# rev2-roadrunner.net
KiCad netlist of a schematic drawn in EAGLE
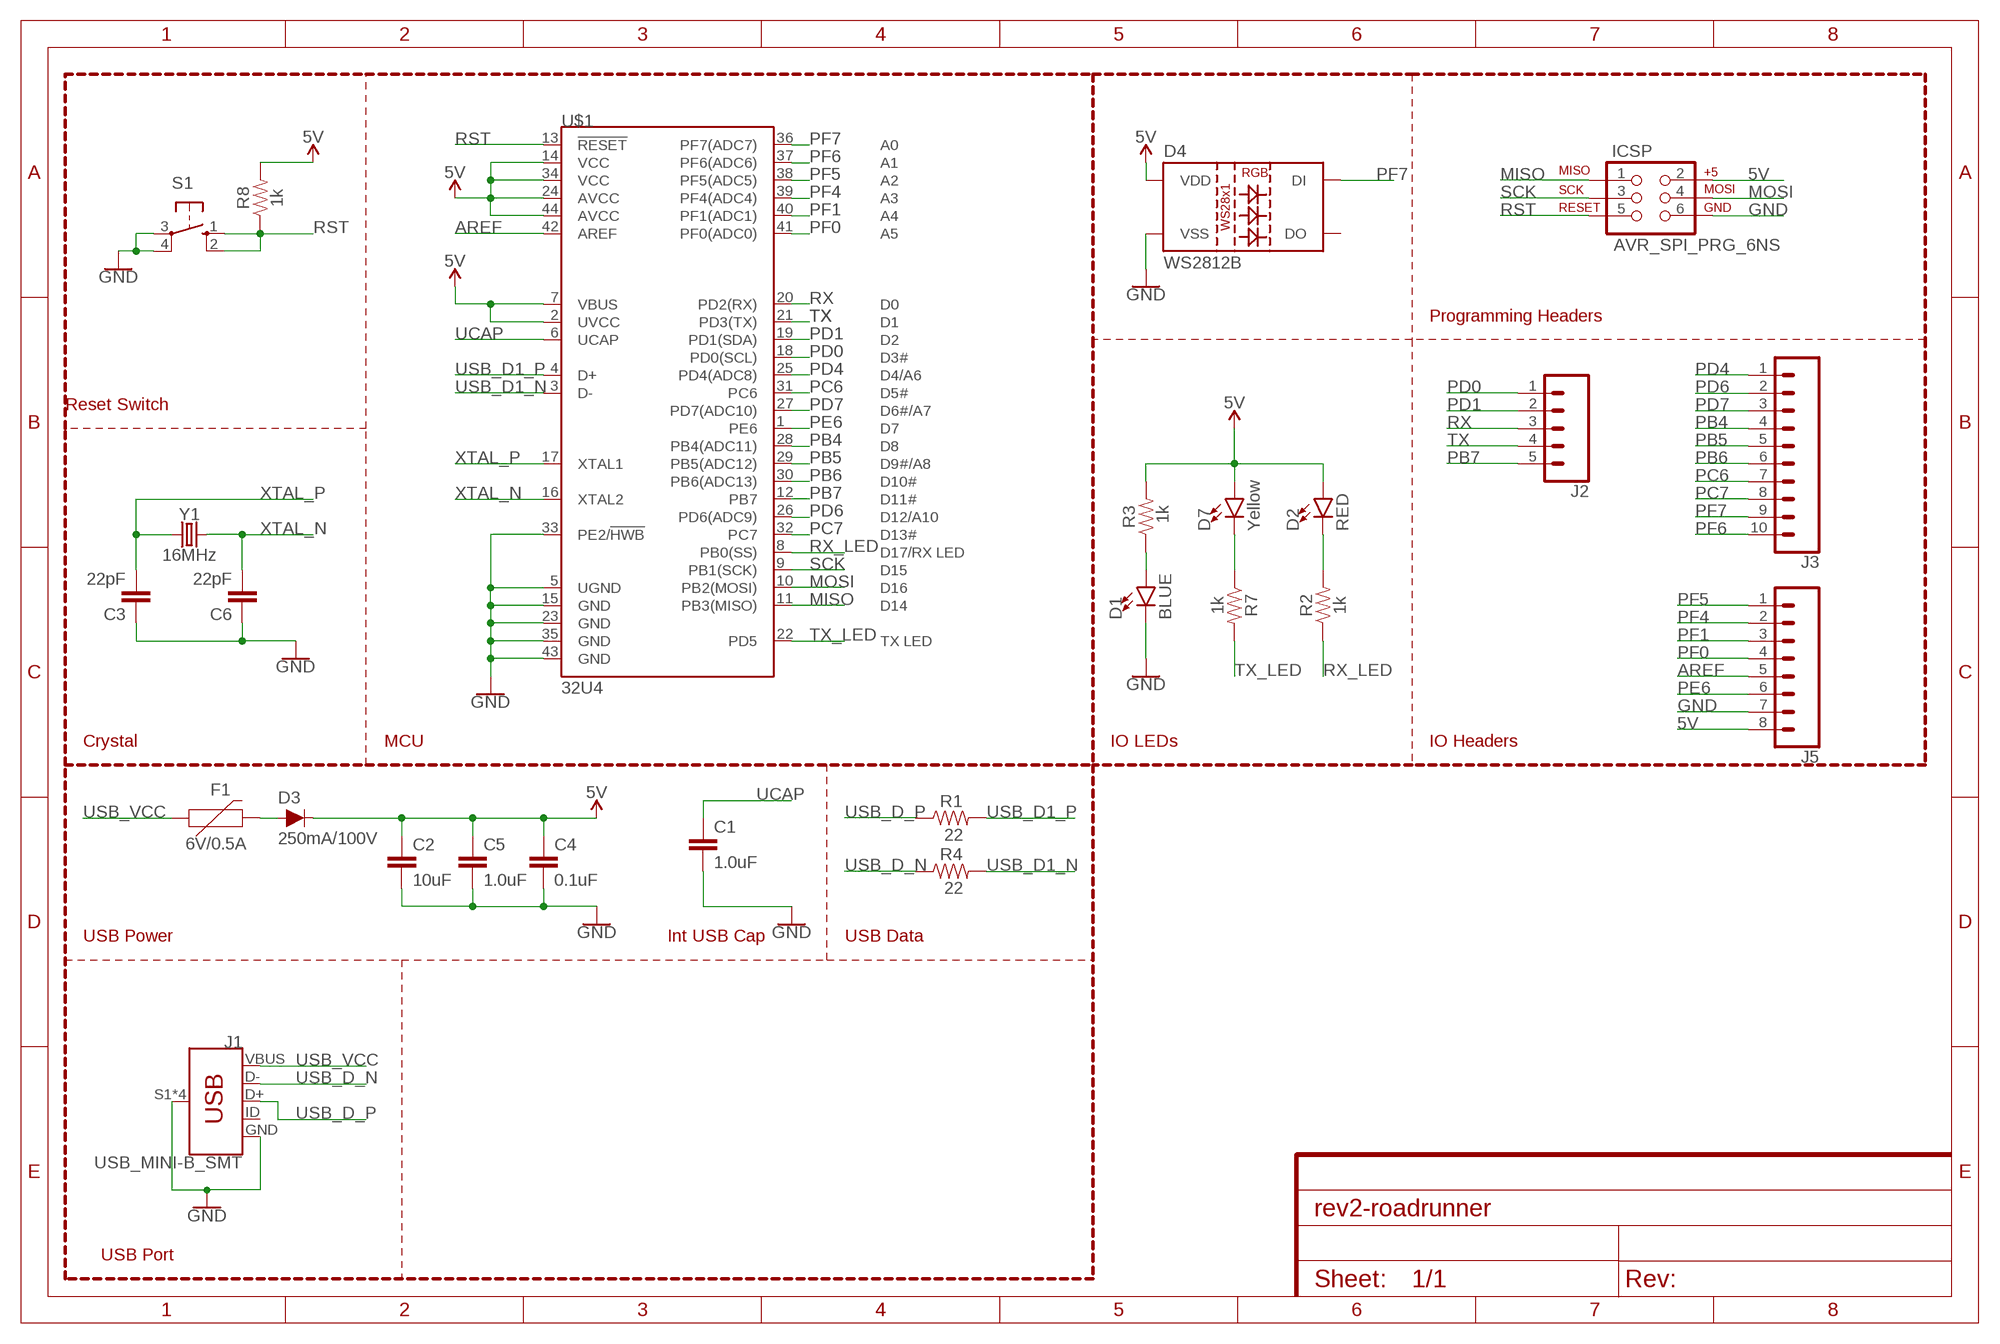
[diagram p0: schematic, sheet 1]

(export (version "E")
  (design (tool "Eeschema 10.0.6"))
  (components
    (comp (ref "C1")
      (value "1.0uF")
      (footprint "eagle-import:1206")
      (libsource (lib "eagle-import") (part "1.0UF-1206-50V-10%"))
    )
    (comp (ref "C2")
      (value "10uF")
      (footprint "eagle-import:1206")
      (libsource (lib "eagle-import") (part "10UF-1206-6.3V-20%"))
    )
    (comp (ref "C3")
      (value "22pF")
      (footprint "eagle-import:1206")
      (libsource (lib "eagle-import") (part "10UF-1206-6.3V-20%"))
    )
    (comp (ref "C4")
      (value "0.1uF")
      (footprint "eagle-import:1206")
      (libsource (lib "eagle-import") (part "1.0UF-1206-50V-10%"))
    )
    (comp (ref "C5")
      (value "1.0uF")
      (footprint "eagle-import:1206")
      (libsource (lib "eagle-import") (part "1.0UF-1206-50V-10%"))
    )
    (comp (ref "C6")
      (value "22pF")
      (footprint "eagle-import:1206")
      (libsource (lib "eagle-import") (part "10UF-1206-6.3V-20%"))
    )
    (comp (ref "D1")
      (value "BLUE")
      (footprint "eagle-import:LED-1206")
      (libsource (lib "eagle-import") (part "LED-BLUE1206"))
    )
    (comp (ref "D2")
      (value "RED")
      (footprint "eagle-import:LED-1206")
      (libsource (lib "eagle-import") (part "LED-RED1206"))
    )
    (comp (ref "D3")
      (value "250mA/100V")
      (footprint "eagle-import:SOD-323")
      (libsource (lib "eagle-import") (part "DIODE-BAS16J"))
    )
    (comp (ref "D4")
      (value "WS2812B")
      (footprint "eagle-import:WS2812B")
      (libsource (lib "eagle-import") (part "WS2812B"))
    )
    (comp (ref "D7")
      (value "Yellow")
      (footprint "eagle-import:LED-1206")
      (libsource (lib "eagle-import") (part "LED-YELLOWLILYPAD"))
    )
    (comp (ref "F1")
      (value "6V/0.5A")
      (footprint "eagle-import:1206")
      (libsource (lib "eagle-import") (part "PPTC_HALF-AMP"))
    )
    (comp (ref "ICSP")
      (value "AVR_SPI_PRG_6NS")
      (footprint "eagle-import:2X3-NS")
      (libsource (lib "eagle-import") (part "AVR_SPI_PRG_6NS"))
    )
    (comp (ref "J1")
      (value "USB_MINI-B_SMT")
      (footprint "eagle-import:USB-MINIB")
      (libsource (lib "eagle-import") (part "USB_MINI-B_SMT"))
    )
    (comp (ref "J2")
      (value "CONN_05")
      (footprint "eagle-import:1X05")
      (libsource (lib "eagle-import") (part "CONN_05"))
    )
    (comp (ref "J3")
      (value "CONN_10\"")
      (footprint "eagle-import:1X10")
      (libsource (lib "eagle-import") (part "CONN_10{dblquote}"))
    )
    (comp (ref "J5")
      (value "CONN_08\"")
      (footprint "eagle-import:1X08")
      (libsource (lib "eagle-import") (part "CONN_08{dblquote}"))
    )
    (comp (ref "R1")
      (value "22")
      (footprint "eagle-import:1206")
      (libsource (lib "eagle-import") (part "RESISTOR1206"))
    )
    (comp (ref "R2")
      (value "1k")
      (footprint "eagle-import:1206")
      (libsource (lib "eagle-import") (part "RESISTOR1206"))
    )
    (comp (ref "R3")
      (value "1k")
      (footprint "eagle-import:1206")
      (libsource (lib "eagle-import") (part "RESISTOR1206"))
    )
    (comp (ref "R4")
      (value "22")
      (footprint "eagle-import:1206")
      (libsource (lib "eagle-import") (part "RESISTOR1206"))
    )
    (comp (ref "R7")
      (value "1k")
      (footprint "eagle-import:1206")
      (libsource (lib "eagle-import") (part "RESISTOR1206"))
    )
    (comp (ref "R8")
      (value "1k")
      (footprint "eagle-import:1206")
      (libsource (lib "eagle-import") (part "RESISTOR1206"))
    )
    (comp (ref "S1")
      (value "10-XX")
      (footprint "eagle-import:B3F-10XX")
      (fields (field (name "MPN") "B3F-1000"))
      (libsource (lib "eagle-import") (part "10-XX"))
    )
    (comp (ref "U$1")
      (value "32U4")
      (footprint "eagle-import:TQFP44")
      (libsource (lib "eagle-import") (part "ATMEGA32U4TQFP-44"))
    )
    (comp (ref "Y1")
      (value "16MHz")
      (footprint "eagle-import:HC49US")
      (libsource (lib "eagle-import") (part "CRYSTAL-16MHZPTH-HC49US"))
    )
  )
  (nets
    (net (code "1") (name "/AREF") (class "Default")
      (node (ref "J5") (pin "5") (pinfunction "5_5") (pintype "passive"))
      (node (ref "U$1") (pin "42") (pinfunction "AREF_42") (pintype "bidirectional"))
    )
    (net (code "2") (name "/MISO") (class "Default")
      (node (ref "ICSP") (pin "1") (pinfunction "1_1") (pintype "passive"))
      (node (ref "U$1") (pin "11") (pinfunction "PB3(MISO)_11") (pintype "bidirectional"))
    )
    (net (code "3") (name "/MOSI") (class "Default")
      (node (ref "ICSP") (pin "4") (pinfunction "4_4") (pintype "passive"))
      (node (ref "U$1") (pin "10") (pinfunction "PB2(MOSI)_10") (pintype "bidirectional"))
    )
    (net (code "4") (name "/PB4") (class "Default")
      (node (ref "J3") (pin "4") (pinfunction "4_4") (pintype "passive"))
      (node (ref "U$1") (pin "28") (pinfunction "PB4(ADC11)_28") (pintype "bidirectional"))
    )
    (net (code "5") (name "/PB5") (class "Default")
      (node (ref "J3") (pin "5") (pinfunction "5_5") (pintype "passive"))
      (node (ref "U$1") (pin "29") (pinfunction "PB5(ADC12)_29") (pintype "bidirectional"))
    )
    (net (code "6") (name "/PB6") (class "Default")
      (node (ref "J3") (pin "6") (pinfunction "6_6") (pintype "passive"))
      (node (ref "U$1") (pin "30") (pinfunction "PB6(ADC13)_30") (pintype "bidirectional"))
    )
    (net (code "7") (name "/PB7") (class "Default")
      (node (ref "J2") (pin "5") (pinfunction "5_5") (pintype "passive"))
      (node (ref "U$1") (pin "12") (pinfunction "PB7_12") (pintype "bidirectional"))
    )
    (net (code "8") (name "/PC6") (class "Default")
      (node (ref "J3") (pin "7") (pinfunction "7_7") (pintype "passive"))
      (node (ref "U$1") (pin "31") (pinfunction "PC6_31") (pintype "bidirectional"))
    )
    (net (code "9") (name "/PC7") (class "Default")
      (node (ref "J3") (pin "8") (pinfunction "8_8") (pintype "passive"))
      (node (ref "U$1") (pin "32") (pinfunction "PC7_32") (pintype "bidirectional"))
    )
    (net (code "10") (name "/PD0") (class "Default")
      (node (ref "J2") (pin "1") (pinfunction "1_1") (pintype "passive"))
      (node (ref "U$1") (pin "18") (pinfunction "PD0(SCL)_18") (pintype "bidirectional"))
    )
    (net (code "11") (name "/PD1") (class "Default")
      (node (ref "J2") (pin "2") (pinfunction "2_2") (pintype "passive"))
      (node (ref "U$1") (pin "19") (pinfunction "PD1(SDA)_19") (pintype "bidirectional"))
    )
    (net (code "12") (name "/PD4") (class "Default")
      (node (ref "J3") (pin "1") (pinfunction "1_1") (pintype "passive"))
      (node (ref "U$1") (pin "25") (pinfunction "PD4(ADC8)_25") (pintype "bidirectional"))
    )
    (net (code "13") (name "/PD6") (class "Default")
      (node (ref "J3") (pin "2") (pinfunction "2_2") (pintype "passive"))
      (node (ref "U$1") (pin "26") (pinfunction "PD6(ADC9)_26") (pintype "bidirectional"))
    )
    (net (code "14") (name "/PD7") (class "Default")
      (node (ref "J3") (pin "3") (pinfunction "3_3") (pintype "passive"))
      (node (ref "U$1") (pin "27") (pinfunction "PD7(ADC10)_27") (pintype "bidirectional"))
    )
    (net (code "15") (name "/PE6") (class "Default")
      (node (ref "J5") (pin "6") (pinfunction "6_6") (pintype "passive"))
      (node (ref "U$1") (pin "1") (pinfunction "PE6_1") (pintype "bidirectional"))
    )
    (net (code "16") (name "/PF0") (class "Default")
      (node (ref "J5") (pin "4") (pinfunction "4_4") (pintype "passive"))
      (node (ref "U$1") (pin "41") (pinfunction "PF0(ADC0)_41") (pintype "bidirectional"))
    )
    (net (code "17") (name "/PF1") (class "Default")
      (node (ref "J5") (pin "3") (pinfunction "3_3") (pintype "passive"))
      (node (ref "U$1") (pin "40") (pinfunction "PF1(ADC1)_40") (pintype "bidirectional"))
    )
    (net (code "18") (name "/PF4") (class "Default")
      (node (ref "J5") (pin "2") (pinfunction "2_2") (pintype "passive"))
      (node (ref "U$1") (pin "39") (pinfunction "PF4(ADC4)_39") (pintype "bidirectional"))
    )
    (net (code "19") (name "/PF5") (class "Default")
      (node (ref "J5") (pin "1") (pinfunction "1_1") (pintype "passive"))
      (node (ref "U$1") (pin "38") (pinfunction "PF5(ADC5)_38") (pintype "bidirectional"))
    )
    (net (code "20") (name "/PF6") (class "Default")
      (node (ref "J3") (pin "10") (pinfunction "10_10") (pintype "passive"))
      (node (ref "U$1") (pin "37") (pinfunction "PF6(ADC6)_37") (pintype "bidirectional"))
    )
    (net (code "21") (name "/PF7") (class "Default")
      (node (ref "D4") (pin "4") (pinfunction "DI_4") (pintype "bidirectional"))
      (node (ref "J3") (pin "9") (pinfunction "9_9") (pintype "passive"))
      (node (ref "U$1") (pin "36") (pinfunction "PF7(ADC7)_36") (pintype "bidirectional"))
    )
    (net (code "22") (name "/RST") (class "Default")
      (node (ref "ICSP") (pin "5") (pinfunction "5_5") (pintype "passive"))
      (node (ref "R8") (pin "1") (pinfunction "1_1") (pintype "passive"))
      (node (ref "S1") (pin "1") (pinfunction "S_1") (pintype "passive"))
      (node (ref "S1") (pin "2") (pinfunction "S1_2") (pintype "passive"))
      (node (ref "U$1") (pin "13") (pinfunction "~{RESET}_13") (pintype "bidirectional"))
    )
    (net (code "23") (name "/RX") (class "Default")
      (node (ref "J2") (pin "3") (pinfunction "3_3") (pintype "passive"))
      (node (ref "U$1") (pin "20") (pinfunction "PD2(RX)_20") (pintype "bidirectional"))
    )
    (net (code "24") (name "/RX_LED") (class "Default")
      (node (ref "R2") (pin "1") (pinfunction "1_1") (pintype "passive"))
      (node (ref "U$1") (pin "8") (pinfunction "PB0(SS)_8") (pintype "bidirectional"))
    )
    (net (code "25") (name "/SCK") (class "Default")
      (node (ref "ICSP") (pin "3") (pinfunction "3_3") (pintype "passive"))
      (node (ref "U$1") (pin "9") (pinfunction "PB1(SCK)_9") (pintype "bidirectional"))
    )
    (net (code "26") (name "/TX") (class "Default")
      (node (ref "J2") (pin "4") (pinfunction "4_4") (pintype "passive"))
      (node (ref "U$1") (pin "21") (pinfunction "PD3(TX)_21") (pintype "bidirectional"))
    )
    (net (code "27") (name "/TX_LED") (class "Default")
      (node (ref "R7") (pin "2") (pinfunction "2_2") (pintype "passive"))
      (node (ref "U$1") (pin "22") (pinfunction "PD5_22") (pintype "bidirectional"))
    )
    (net (code "28") (name "/UCAP") (class "Default")
      (node (ref "C1") (pin "1") (pinfunction "1_1") (pintype "passive"))
      (node (ref "U$1") (pin "6") (pinfunction "UCAP_6") (pintype "bidirectional"))
    )
    (net (code "29") (name "/USB_D1_N") (class "Default")
      (node (ref "R4") (pin "2") (pinfunction "2_2") (pintype "passive"))
      (node (ref "U$1") (pin "3") (pinfunction "D-_3") (pintype "bidirectional"))
    )
    (net (code "30") (name "/USB_D1_P") (class "Default")
      (node (ref "R1") (pin "2") (pinfunction "2_2") (pintype "passive"))
      (node (ref "U$1") (pin "4") (pinfunction "D+_4") (pintype "bidirectional"))
    )
    (net (code "31") (name "/USB_D_N") (class "Default")
      (node (ref "J1") (pin "D-") (pinfunction "D-_D-") (pintype "bidirectional"))
      (node (ref "R4") (pin "1") (pinfunction "1_1") (pintype "passive"))
    )
    (net (code "32") (name "/USB_D_P") (class "Default")
      (node (ref "J1") (pin "D+") (pinfunction "D+_D+") (pintype "bidirectional"))
      (node (ref "R1") (pin "1") (pinfunction "1_1") (pintype "passive"))
    )
    (net (code "33") (name "/USB_VCC") (class "Default")
      (node (ref "F1") (pin "1") (pinfunction "1_1") (pintype "bidirectional"))
      (node (ref "J1") (pin "VBUS") (pinfunction "VBUS_VBUS") (pintype "power_in"))
    )
    (net (code "34") (name "/XTAL_N") (class "Default")
      (node (ref "C6") (pin "2") (pinfunction "2_2") (pintype "passive"))
      (node (ref "U$1") (pin "16") (pinfunction "XTAL2_16") (pintype "bidirectional"))
      (node (ref "Y1") (pin "2") (pinfunction "2_2") (pintype "passive"))
    )
    (net (code "35") (name "/XTAL_P") (class "Default")
      (node (ref "C3") (pin "2") (pinfunction "2_2") (pintype "passive"))
      (node (ref "U$1") (pin "17") (pinfunction "XTAL1_17") (pintype "bidirectional"))
      (node (ref "Y1") (pin "1") (pinfunction "1_1") (pintype "passive"))
    )
    (net (code "36") (name "5V") (class "Default")
      (node (ref "C2") (pin "1") (pinfunction "1_1") (pintype "passive"))
      (node (ref "C4") (pin "1") (pinfunction "1_1") (pintype "passive"))
      (node (ref "C5") (pin "1") (pinfunction "1_1") (pintype "passive"))
      (node (ref "D2") (pin "A") (pinfunction "A_A") (pintype "passive"))
      (node (ref "D3") (pin "C") (pinfunction "C_C") (pintype "passive"))
      (node (ref "D4") (pin "1") (pinfunction "VDD_1") (pintype "bidirectional"))
      (node (ref "D7") (pin "A") (pinfunction "A_A") (pintype "passive"))
      (node (ref "ICSP") (pin "2") (pinfunction "2_2") (pintype "passive"))
      (node (ref "J5") (pin "8") (pinfunction "8_8") (pintype "passive"))
      (node (ref "R3") (pin "2") (pinfunction "2_2") (pintype "passive"))
      (node (ref "R8") (pin "2") (pinfunction "2_2") (pintype "passive"))
      (node (ref "U$1") (pin "14") (pinfunction "VCC_14") (pintype "bidirectional"))
      (node (ref "U$1") (pin "2") (pinfunction "UVCC_2") (pintype "bidirectional"))
      (node (ref "U$1") (pin "24") (pinfunction "AVCC_24") (pintype "bidirectional"))
      (node (ref "U$1") (pin "34") (pinfunction "VCC_34") (pintype "bidirectional"))
      (node (ref "U$1") (pin "44") (pinfunction "AVCC_44") (pintype "bidirectional"))
      (node (ref "U$1") (pin "7") (pinfunction "VBUS_7") (pintype "bidirectional"))
    )
    (net (code "37") (name "GND") (class "Default")
      (node (ref "C1") (pin "2") (pinfunction "2_2") (pintype "passive"))
      (node (ref "C2") (pin "2") (pinfunction "2_2") (pintype "passive"))
      (node (ref "C3") (pin "1") (pinfunction "1_1") (pintype "passive"))
      (node (ref "C4") (pin "2") (pinfunction "2_2") (pintype "passive"))
      (node (ref "C5") (pin "2") (pinfunction "2_2") (pintype "passive"))
      (node (ref "C6") (pin "1") (pinfunction "1_1") (pintype "passive"))
      (node (ref "D1") (pin "C") (pinfunction "C_C") (pintype "passive"))
      (node (ref "D4") (pin "3") (pinfunction "VSS_3") (pintype "bidirectional"))
      (node (ref "ICSP") (pin "6") (pinfunction "6_6") (pintype "passive"))
      (node (ref "J1") (pin "GND") (pinfunction "GND_GND") (pintype "power_in"))
      (node (ref "J1") (pin "S1") (pinfunction "SHIELD_S1") (pintype "bidirectional"))
      (node (ref "J1") (pin "S2") (pinfunction "SHIELD_S2") (pintype "bidirectional"))
      (node (ref "J1") (pin "S3") (pinfunction "SHIELD_S3") (pintype "bidirectional"))
      (node (ref "J1") (pin "S4") (pinfunction "SHIELD_S4") (pintype "bidirectional"))
      (node (ref "J5") (pin "7") (pinfunction "7_7") (pintype "passive"))
      (node (ref "S1") (pin "3") (pinfunction "P_3") (pintype "passive"))
      (node (ref "S1") (pin "4") (pinfunction "P1_4") (pintype "passive"))
      (node (ref "U$1") (pin "15") (pinfunction "GND_15") (pintype "bidirectional"))
      (node (ref "U$1") (pin "23") (pinfunction "GND_23") (pintype "bidirectional"))
      (node (ref "U$1") (pin "33") (pinfunction "PE2/~{HWB}_33") (pintype "bidirectional"))
      (node (ref "U$1") (pin "35") (pinfunction "GND_35") (pintype "bidirectional"))
      (node (ref "U$1") (pin "43") (pinfunction "GND_43") (pintype "bidirectional"))
      (node (ref "U$1") (pin "5") (pinfunction "UGND_5") (pintype "bidirectional"))
    )
    (net (code "38") (name "Net-(D1-PadA)") (class "Default")
      (node (ref "D1") (pin "A") (pinfunction "A_A") (pintype "passive"))
      (node (ref "R3") (pin "1") (pinfunction "1_1") (pintype "passive"))
    )
    (net (code "39") (name "Net-(D2-PadC)") (class "Default")
      (node (ref "D2") (pin "C") (pinfunction "C_C") (pintype "passive"))
      (node (ref "R2") (pin "2") (pinfunction "2_2") (pintype "passive"))
    )
    (net (code "40") (name "Net-(D3-PadA)") (class "Default")
      (node (ref "D3") (pin "A") (pinfunction "A_A") (pintype "passive"))
      (node (ref "F1") (pin "2") (pinfunction "2_2") (pintype "bidirectional"))
    )
    (net (code "41") (name "Net-(D7-PadC)") (class "Default")
      (node (ref "D7") (pin "C") (pinfunction "C_C") (pintype "passive"))
      (node (ref "R7") (pin "1") (pinfunction "1_1") (pintype "passive"))
    )
    (net (code "42") (name "unconnected-(D4-DO-Pad2)") (class "Default")
      (node (ref "D4") (pin "2") (pinfunction "DO_2") (pintype "bidirectional"))
    )
    (net (code "43") (name "unconnected-(J1-PadID)") (class "Default")
      (node (ref "J1") (pin "ID") (pinfunction "ID_ID") (pintype "bidirectional"))
    )
  )
)
